# ExampleSch.net
KiCad netlist of a schematic drawn in Altium Designer
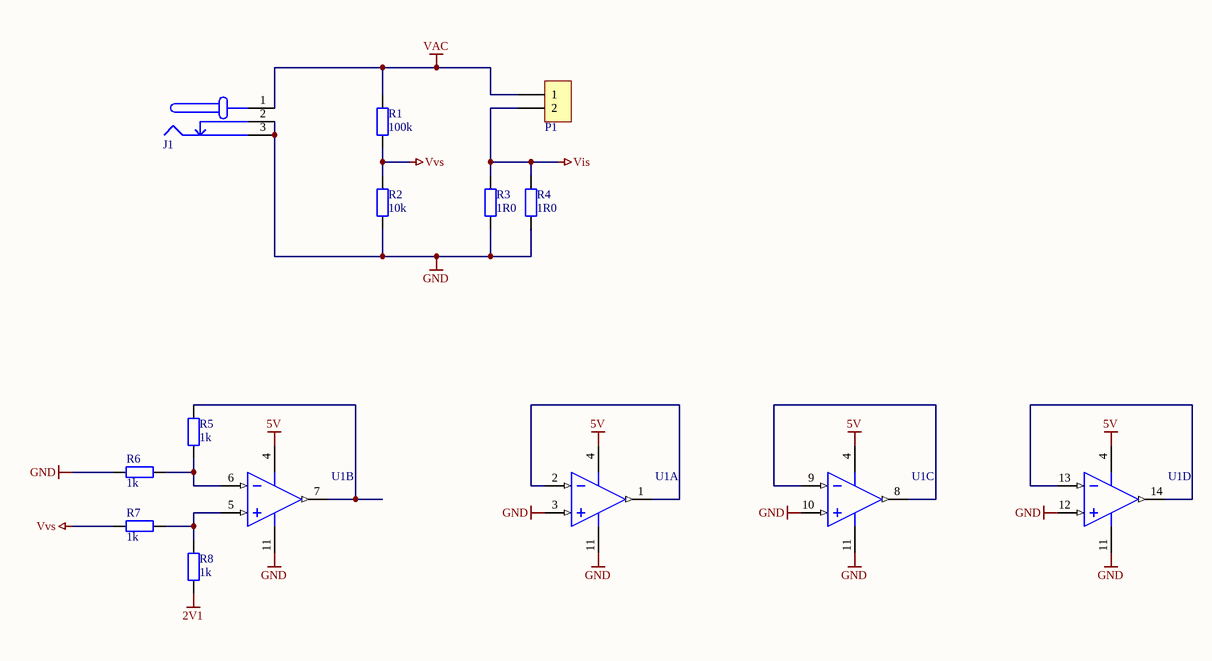
[diagram p0: ExampleSch.SchDoc]

(export (version "E")
  (design (tool "Eeschema 10.0.6"))
  (components
    (comp (ref "J1")
      (value "DC barrel jack")
      (footprint "AC-Socket")
      (description "DC barrel jack connection to AC source")
      (libsource (lib "EE209_Library") (part "AC_Input"))
    )
    (comp (ref "P1")
      (value "Dual Banana Plugs")
      (footprint "Dual Banana Plug")
      (description "Dual banana plugs connection to the AC load")
      (fields (field (name "PUBLISHER") "Altium Limited"))
      (libsource (lib "EE209_Library") (part "AC_Output"))
    )
    (comp (ref "R1")
      (value "100k")
      (footprint "AXIAL-0.4")
      (description "Through hole resistor")
      (fields (field (name "PUBLISHER") "Altium Limited"))
      (libsource (lib "") (part "Res_TH_0AX4_1"))
    )
    (comp (ref "R2")
      (value "10k")
      (footprint "AXIAL-0.4")
      (description "Through hole resistor")
      (fields (field (name "PUBLISHER") "Altium Limited"))
      (libsource (lib "EE209_Library") (part "Res_TH_0AX4"))
    )
    (comp (ref "R3")
      (value "1R0")
      (footprint "AXIAL-0.4")
      (description "Through hole resistor")
      (fields (field (name "PUBLISHER") "Altium Limited"))
      (libsource (lib "") (part "Res_TH_0AX4_1"))
    )
    (comp (ref "R4")
      (value "1R0")
      (footprint "AXIAL-0.4")
      (description "Through hole resistor")
      (fields (field (name "PUBLISHER") "Altium Limited"))
      (libsource (lib "") (part "Res_TH_0AX4_1"))
    )
    (comp (ref "R5")
      (value "1k")
      (footprint "AXIAL-0.4")
      (description "Through hole resistor")
      (fields (field (name "PUBLISHER") "Altium Limited"))
      (libsource (lib "EE209_Library") (part "Res_TH_0AX4"))
    )
    (comp (ref "R6")
      (value "1k")
      (footprint "AXIAL-0.4")
      (description "Through hole resistor")
      (fields (field (name "PUBLISHER") "Altium Limited"))
      (libsource (lib "") (part "Res_TH_0AX4_2"))
    )
    (comp (ref "R7")
      (value "1k")
      (footprint "AXIAL-0.4")
      (description "Through hole resistor")
      (fields (field (name "PUBLISHER") "Altium Limited"))
      (libsource (lib "") (part "Res_TH_0AX4_2"))
    )
    (comp (ref "R8")
      (value "1k")
      (footprint "AXIAL-0.4")
      (description "Through hole resistor")
      (fields (field (name "PUBLISHER") "Altium Limited"))
      (libsource (lib "EE209_Library") (part "Res_TH_0AX4"))
    )
    (comp (ref "U1")
      (value "LM324")
      (footprint "DIP-14")
      (description "IC OPAMP GP 14DIP")
      (fields
        (field (name "MANUFACTURER") "ON Semiconductor")
        (field (name "MANUFACTURER PART NUMBER") "LM324N")
      )
      (libsource (lib "EE209_Library") (part "LM324N_TH_DIP16"))
    )
  )
  (nets
    (net (code "1") (name "2V1") (class "Default")
      (node (ref "R8") (pin "1") (pinfunction "1_1") (pintype "passive"))
    )
    (net (code "2") (name "5V") (class "Default")
      (node (ref "U1") (pin "4") (pinfunction "VDD_4") (pintype "power_in"))
    )
    (net (code "3") (name "GND") (class "Default")
      (node (ref "J1") (pin "2") (pinfunction "GND_ALT_2") (pintype "power_in"))
      (node (ref "J1") (pin "3") (pinfunction "GND_3") (pintype "power_in"))
      (node (ref "R2") (pin "1") (pinfunction "1_1") (pintype "passive"))
      (node (ref "R3") (pin "2") (pinfunction "2_2") (pintype "passive"))
      (node (ref "R4") (pin "2") (pinfunction "2_2") (pintype "passive"))
      (node (ref "R6") (pin "1") (pinfunction "1_1") (pintype "passive"))
      (node (ref "U1") (pin "10") (pinfunction "VINC+_10") (pintype "input"))
      (node (ref "U1") (pin "11") (pinfunction "VSS_11") (pintype "power_in"))
      (node (ref "U1") (pin "12") (pinfunction "VIND+_12") (pintype "input"))
      (node (ref "U1") (pin "3") (pinfunction "VINA+_3") (pintype "input"))
    )
    (net (code "4") (name "Net-(U1A-VINA-)") (class "Default")
      (node (ref "U1") (pin "1") (pinfunction "VOUTA_1") (pintype "output"))
      (node (ref "U1") (pin "2") (pinfunction "VINA-_2") (pintype "input"))
    )
    (net (code "5") (name "Net-(U1B-VINB+)") (class "Default")
      (node (ref "R7") (pin "2") (pinfunction "2_2") (pintype "passive"))
      (node (ref "R8") (pin "2") (pinfunction "2_2") (pintype "passive"))
      (node (ref "U1") (pin "5") (pinfunction "VINB+_5") (pintype "input"))
    )
    (net (code "6") (name "Net-(U1B-VINB-)") (class "Default")
      (node (ref "R5") (pin "1") (pinfunction "1_1") (pintype "passive"))
      (node (ref "R6") (pin "2") (pinfunction "2_2") (pintype "passive"))
      (node (ref "U1") (pin "6") (pinfunction "VINB-_6") (pintype "input"))
    )
    (net (code "7") (name "Net-(U1B-VOUTB)") (class "Default")
      (node (ref "R5") (pin "2") (pinfunction "2_2") (pintype "passive"))
      (node (ref "U1") (pin "7") (pinfunction "VOUTB_7") (pintype "output"))
    )
    (net (code "8") (name "Net-(U1C-VINC-)") (class "Default")
      (node (ref "U1") (pin "8") (pinfunction "VOUTC_8") (pintype "output"))
      (node (ref "U1") (pin "9") (pinfunction "VINC-_9") (pintype "input"))
    )
    (net (code "9") (name "Net-(U1D-VIND-)") (class "Default")
      (node (ref "U1") (pin "13") (pinfunction "VIND-_13") (pintype "input"))
      (node (ref "U1") (pin "14") (pinfunction "VOUTD_14") (pintype "output"))
    )
    (net (code "10") (name "VAC") (class "Default")
      (node (ref "J1") (pin "1") (pinfunction "VCC_1") (pintype "power_in"))
      (node (ref "P1") (pin "1") (pinfunction "1_1") (pintype "passive"))
      (node (ref "R1") (pin "1") (pinfunction "1_1") (pintype "passive"))
    )
    (net (code "11") (name "Vis") (class "Default")
      (node (ref "P1") (pin "2") (pinfunction "2_2") (pintype "passive"))
      (node (ref "R3") (pin "1") (pinfunction "1_1") (pintype "passive"))
      (node (ref "R4") (pin "1") (pinfunction "1_1") (pintype "passive"))
    )
    (net (code "12") (name "Vvs") (class "Default")
      (node (ref "R1") (pin "2") (pinfunction "2_2") (pintype "passive"))
      (node (ref "R2") (pin "2") (pinfunction "2_2") (pintype "passive"))
      (node (ref "R7") (pin "1") (pinfunction "1_1") (pintype "passive"))
    )
  )
)
